# MKS_V5_SMOOTHER_v2.net
KiCad netlist of a schematic drawn in EAGLE
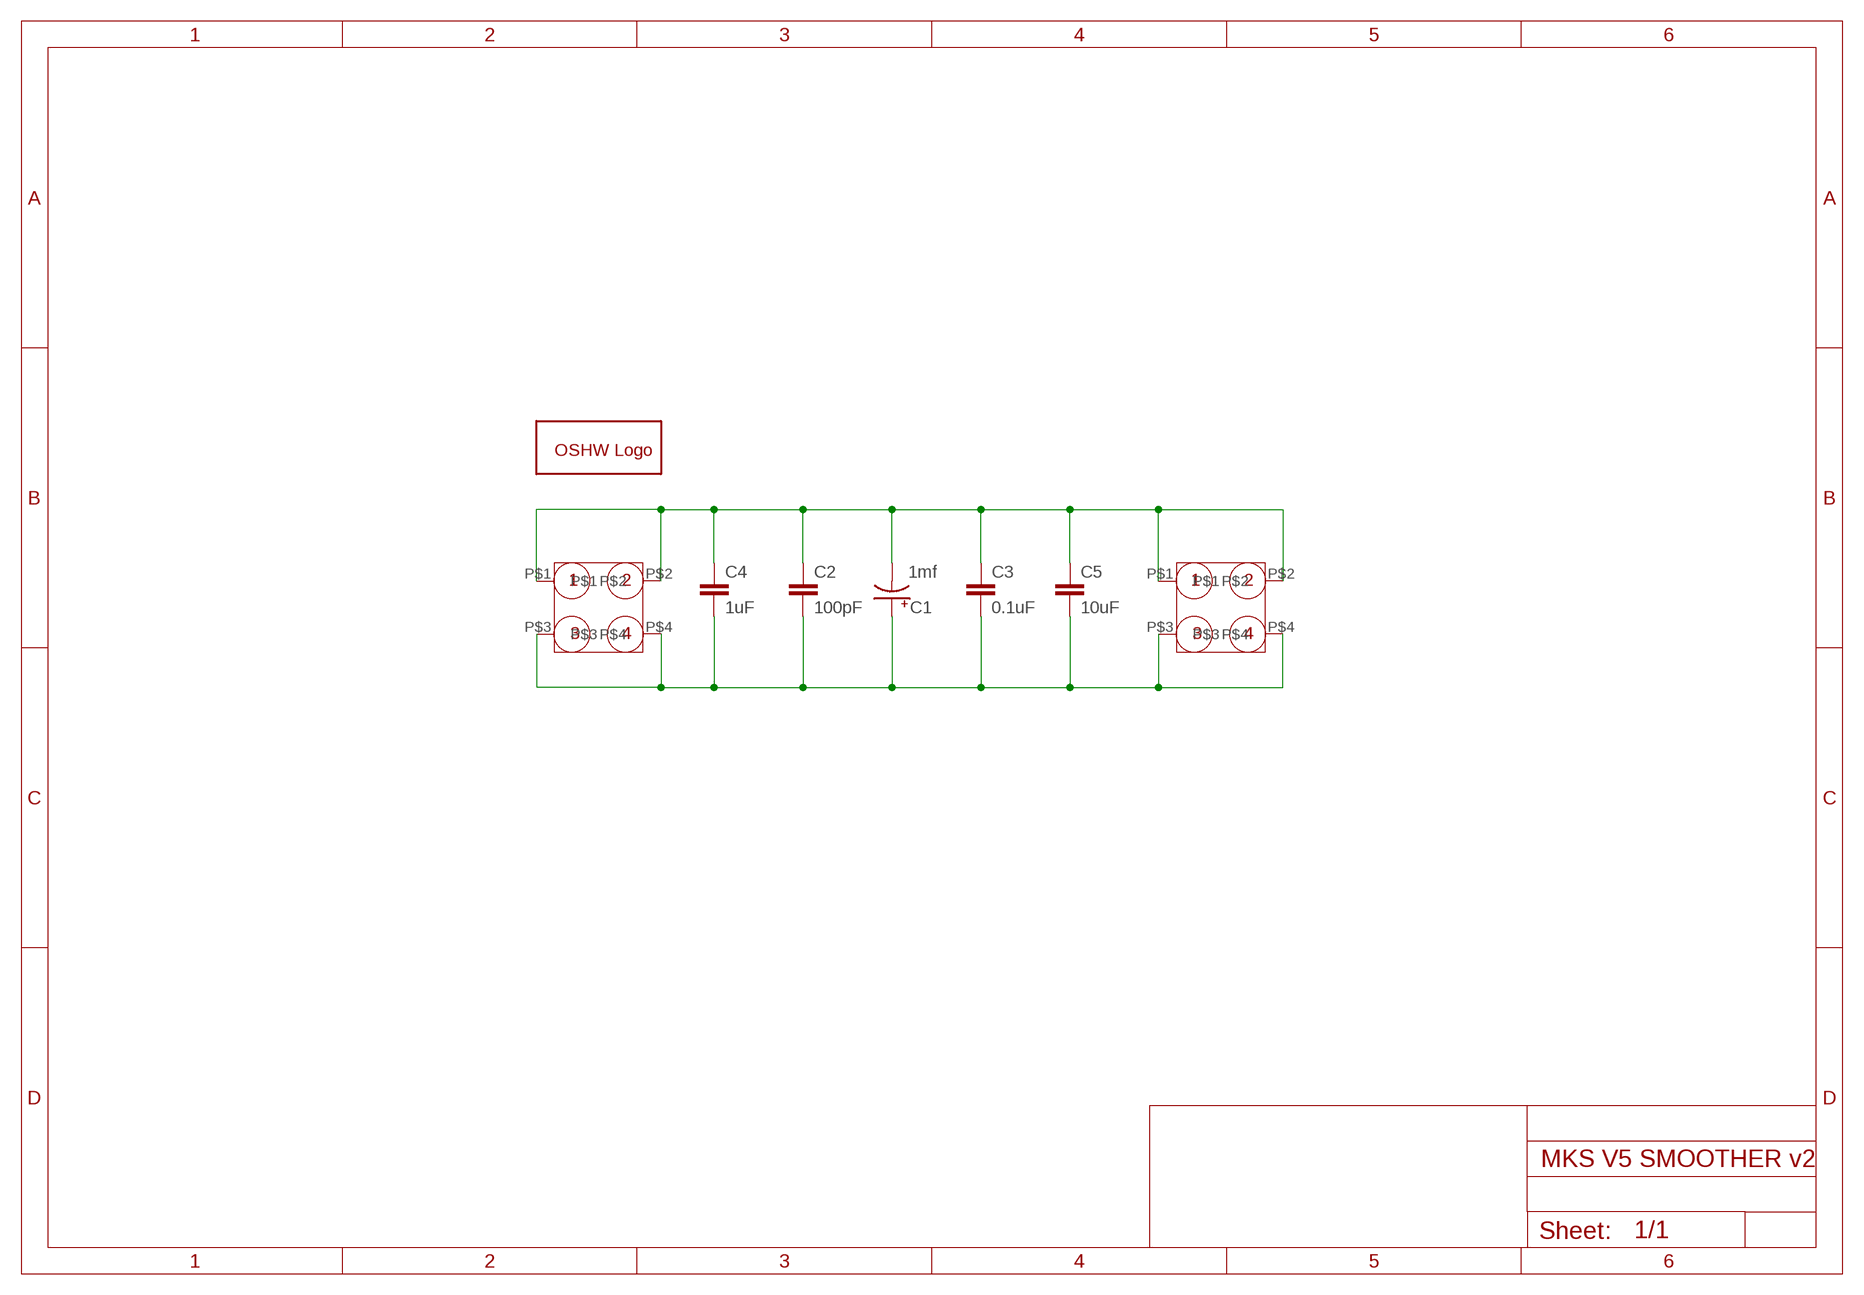
[diagram p0: schematic, sheet 1]

(export (version "E")
  (design (tool "Eeschema 10.0.6"))
  (components
    (comp (ref "C1")
      (value "1mf")
      (footprint "eagle-import:CPOL-RADIAL-5MM-10MM-KIT")
      (libsource (lib "eagle-import") (part "1000UF-RADIAL-5MM-35V-20%-KIT"))
    )
    (comp (ref "C2")
      (value "100pF")
      (footprint "eagle-import:0603")
      (libsource (lib "eagle-import") (part "100PF-0603-50V-5%"))
    )
    (comp (ref "C3")
      (value "0.1uF")
      (footprint "eagle-import:0603")
      (libsource (lib "eagle-import") (part "0.1UF-0603-100V-10%"))
    )
    (comp (ref "C4")
      (value "1uF")
      (footprint "eagle-import:C0805K")
      (libsource (lib "eagle-import") (part "C-EUC0805K"))
    )
    (comp (ref "C5")
      (value "10uF")
      (footprint "eagle-import:C0805K")
      (libsource (lib "eagle-import") (part "C-EUC0805K"))
    )
    (comp (ref "GOLD_ORB_SM1")
      (value "OSHWLOGOLOGO5MM")
      (footprint "eagle-import:OSHW_5MM")
      (libsource (lib "eagle-import") (part "OSHWLOGOLOGO5MM"))
    )
    (comp (ref "U$1")
      (value "4BLOCK254")
      (footprint "eagle-import:4BLOCK254")
      (libsource (lib "eagle-import") (part "4BLOCK254"))
    )
    (comp (ref "U$2")
      (value "4BLOCK254")
      (footprint "eagle-import:4BLOCK254")
      (libsource (lib "eagle-import") (part "4BLOCK254"))
    )
  )
  (nets
    (net (code "1") (name "Net-(C1-Pad+)") (class "Default")
      (node (ref "C1") (pin "+") (pinfunction "+_+") (pintype "passive"))
      (node (ref "C2") (pin "2") (pinfunction "2_2") (pintype "passive"))
      (node (ref "C3") (pin "2") (pinfunction "2_2") (pintype "passive"))
      (node (ref "C4") (pin "2") (pinfunction "2_2") (pintype "passive"))
      (node (ref "C5") (pin "2") (pinfunction "2_2") (pintype "passive"))
      (node (ref "U$1") (pin "P$3") (pinfunction "P$3_P$3") (pintype "bidirectional"))
      (node (ref "U$1") (pin "P$4") (pinfunction "P$4_P$4") (pintype "bidirectional"))
      (node (ref "U$2") (pin "P$3") (pinfunction "P$3_P$3") (pintype "bidirectional"))
      (node (ref "U$2") (pin "P$4") (pinfunction "P$4_P$4") (pintype "bidirectional"))
    )
    (net (code "2") (name "Net-(C1-Pad-)") (class "Default")
      (node (ref "C1") (pin "-") (pinfunction "-_-") (pintype "passive"))
      (node (ref "C2") (pin "1") (pinfunction "1_1") (pintype "passive"))
      (node (ref "C3") (pin "1") (pinfunction "1_1") (pintype "passive"))
      (node (ref "C4") (pin "1") (pinfunction "1_1") (pintype "passive"))
      (node (ref "C5") (pin "1") (pinfunction "1_1") (pintype "passive"))
      (node (ref "U$1") (pin "P$1") (pinfunction "P$1_P$1") (pintype "bidirectional"))
      (node (ref "U$1") (pin "P$2") (pinfunction "P$2_P$2") (pintype "bidirectional"))
      (node (ref "U$2") (pin "P$1") (pinfunction "P$1_P$1") (pintype "bidirectional"))
      (node (ref "U$2") (pin "P$2") (pinfunction "P$2_P$2") (pintype "bidirectional"))
    )
  )
)
